# 01-MCU.net
KiCad netlist of a schematic drawn in Altium Designer
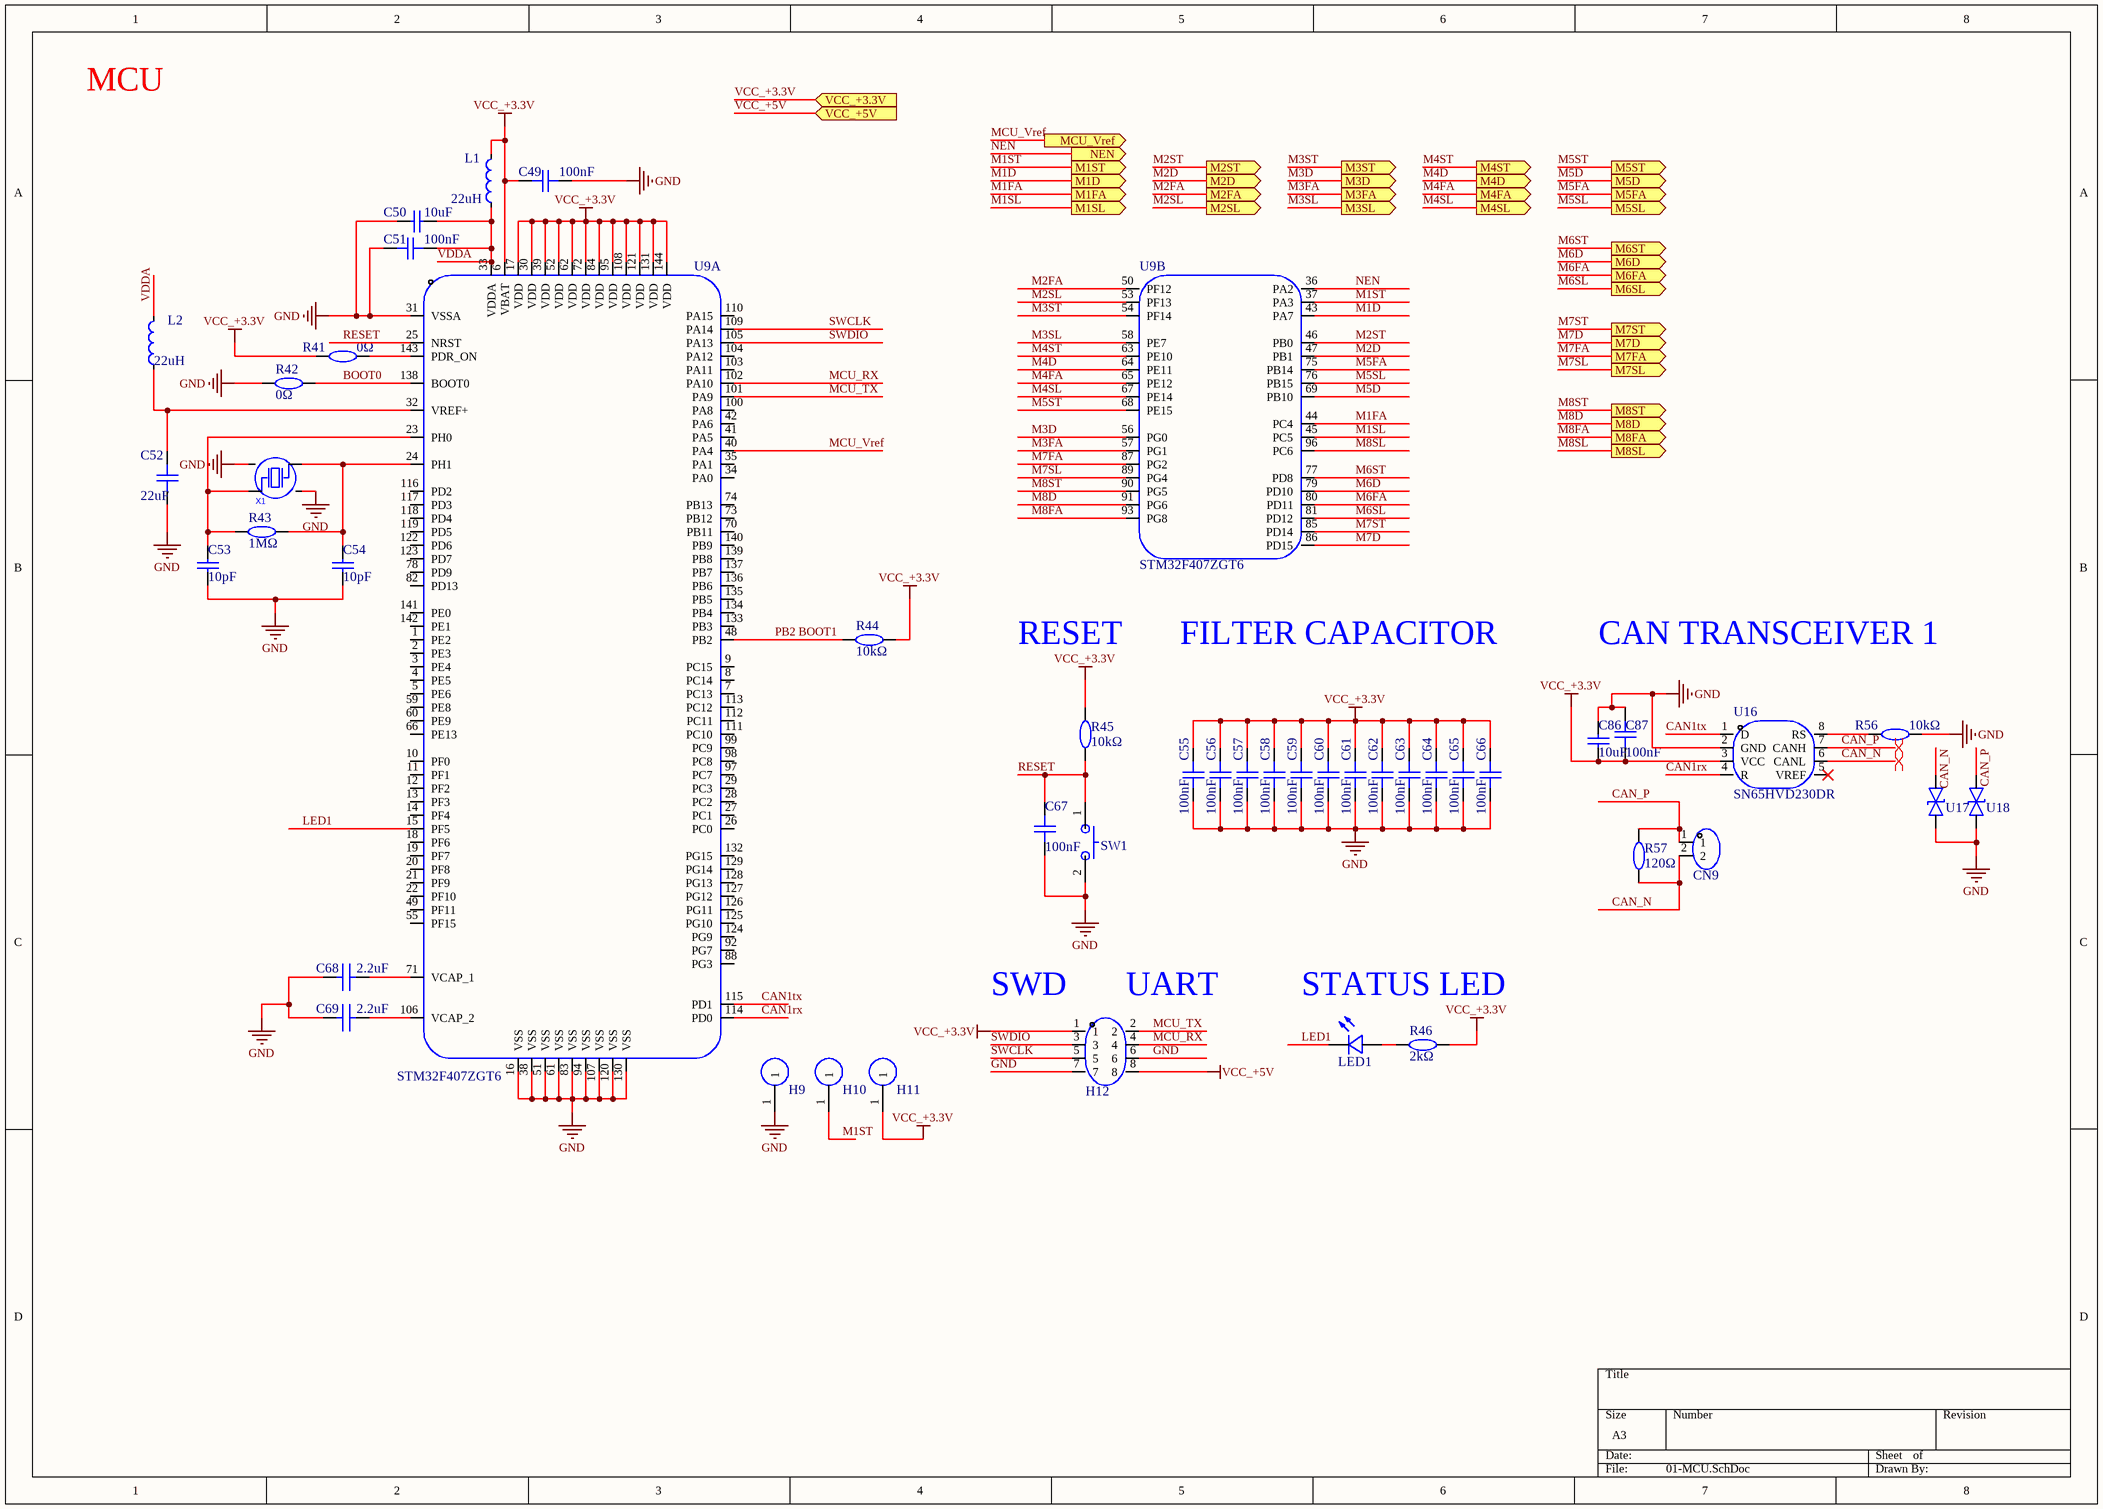
[diagram p0: 01-MCU.SchDoc]

(export (version "E")
  (design (tool "Eeschema 10.0.6"))
  (components
    (comp (ref "C49")
      (value "100nF")
      (footprint "C0402_2.2uF")
      (description "0402电容")
      (fields
        (field (name "MANUFACTURER") "muRata(村田)")
        (field (name "MANUFACTURER PART") "GRM155R71H104KE14D")
      )
      (libsource (lib "SchLib") (part "C0402_100nF"))
    )
    (comp (ref "C50")
      (value "10uF")
      (footprint "C0402_2.2uF")
      (description "0402电容")
      (fields
        (field (name "MANUFACTURER") "SAMSUNG(三星)")
        (field (name "MANUFACTURER PART") "CL05A106MQ5NUNC")
      )
      (libsource (lib "SchLib") (part "C0402_10uF"))
    )
    (comp (ref "C51")
      (value "100nF")
      (footprint "C0402_2.2uF")
      (description "0402电容")
      (fields
        (field (name "MANUFACTURER") "muRata(村田)")
        (field (name "MANUFACTURER PART") "GRM155R71H104KE14D")
      )
      (libsource (lib "SchLib") (part "C0402_100nF"))
    )
    (comp (ref "C52")
      (value "22uF")
      (footprint "C0603")
      (description "0603电容")
      (fields
        (field (name "MANUFACTURER") "SAMSUNG(三星)")
        (field (name "MANUFACTURER PART") "CC0603KRX7R9BB104")
      )
      (libsource (lib "SchLib") (part "C0603_22uF"))
    )
    (comp (ref "C53")
      (value "10pF")
      (footprint "C0402_2.2uF")
      (description "0402电容")
      (fields (field (name "MANUFACTURER") "FH(风华)") (field (name "MANUFACTURER PART") "0402CG100J500NT"))
      (libsource (lib "SchLib") (part "C0402_10pF"))
    )
    (comp (ref "C54")
      (value "10pF")
      (footprint "C0402_2.2uF")
      (description "0402电容")
      (fields (field (name "MANUFACTURER") "FH(风华)") (field (name "MANUFACTURER PART") "0402CG100J500NT"))
      (libsource (lib "SchLib") (part "C0402_10pF"))
    )
    (comp (ref "C55")
      (value "100nF")
      (footprint "C0402_2.2uF")
      (description "0402电容")
      (fields
        (field (name "MANUFACTURER") "muRata(村田)")
        (field (name "MANUFACTURER PART") "GRM155R71H104KE14D")
      )
      (libsource (lib "SchLib") (part "C0402_100nF"))
    )
    (comp (ref "C56")
      (value "100nF")
      (footprint "C0402_2.2uF")
      (description "0402电容")
      (fields
        (field (name "MANUFACTURER") "muRata(村田)")
        (field (name "MANUFACTURER PART") "GRM155R71H104KE14D")
      )
      (libsource (lib "SchLib") (part "C0402_100nF"))
    )
    (comp (ref "C57")
      (value "100nF")
      (footprint "C0402_2.2uF")
      (description "0402电容")
      (fields
        (field (name "MANUFACTURER") "muRata(村田)")
        (field (name "MANUFACTURER PART") "GRM155R71H104KE14D")
      )
      (libsource (lib "SchLib") (part "C0402_100nF"))
    )
    (comp (ref "C58")
      (value "100nF")
      (footprint "C0402_2.2uF")
      (description "0402电容")
      (fields
        (field (name "MANUFACTURER") "muRata(村田)")
        (field (name "MANUFACTURER PART") "GRM155R71H104KE14D")
      )
      (libsource (lib "SchLib") (part "C0402_100nF"))
    )
    (comp (ref "C59")
      (value "100nF")
      (footprint "C0402_2.2uF")
      (description "0402电容")
      (fields
        (field (name "MANUFACTURER") "muRata(村田)")
        (field (name "MANUFACTURER PART") "GRM155R71H104KE14D")
      )
      (libsource (lib "SchLib") (part "C0402_100nF"))
    )
    (comp (ref "C60")
      (value "100nF")
      (footprint "C0402_2.2uF")
      (description "0402电容")
      (fields
        (field (name "MANUFACTURER") "muRata(村田)")
        (field (name "MANUFACTURER PART") "GRM155R71H104KE14D")
      )
      (libsource (lib "SchLib") (part "C0402_100nF"))
    )
    (comp (ref "C61")
      (value "100nF")
      (footprint "C0402_2.2uF")
      (description "0402电容")
      (fields
        (field (name "MANUFACTURER") "muRata(村田)")
        (field (name "MANUFACTURER PART") "GRM155R71H104KE14D")
      )
      (libsource (lib "SchLib") (part "C0402_100nF"))
    )
    (comp (ref "C62")
      (value "100nF")
      (footprint "C0402_2.2uF")
      (description "0402电容")
      (fields
        (field (name "MANUFACTURER") "muRata(村田)")
        (field (name "MANUFACTURER PART") "GRM155R71H104KE14D")
      )
      (libsource (lib "SchLib") (part "C0402_100nF"))
    )
    (comp (ref "C63")
      (value "100nF")
      (footprint "C0402_2.2uF")
      (description "0402电容")
      (fields
        (field (name "MANUFACTURER") "muRata(村田)")
        (field (name "MANUFACTURER PART") "GRM155R71H104KE14D")
      )
      (libsource (lib "SchLib") (part "C0402_100nF"))
    )
    (comp (ref "C64")
      (value "100nF")
      (footprint "C0402_2.2uF")
      (description "0402电容")
      (fields
        (field (name "MANUFACTURER") "muRata(村田)")
        (field (name "MANUFACTURER PART") "GRM155R71H104KE14D")
      )
      (libsource (lib "SchLib") (part "C0402_100nF"))
    )
    (comp (ref "C65")
      (value "100nF")
      (footprint "C0402_2.2uF")
      (description "0402电容")
      (fields
        (field (name "MANUFACTURER") "muRata(村田)")
        (field (name "MANUFACTURER PART") "GRM155R71H104KE14D")
      )
      (libsource (lib "SchLib") (part "C0402_100nF"))
    )
    (comp (ref "C66")
      (value "100nF")
      (footprint "C0402_2.2uF")
      (description "0402电容")
      (fields
        (field (name "MANUFACTURER") "muRata(村田)")
        (field (name "MANUFACTURER PART") "GRM155R71H104KE14D")
      )
      (libsource (lib "SchLib") (part "C0402_100nF"))
    )
    (comp (ref "C67")
      (value "100nF")
      (footprint "C0603")
      (description "0603电容")
      (fields
        (field (name "MANUFACTURER") "SAMSUNG(三星)")
        (field (name "MANUFACTURER PART") "CC0603KRX7R9BB104")
      )
      (libsource (lib "SchLib") (part "C0603_100nF"))
    )
    (comp (ref "C68")
      (value "2.2uF")
      (footprint "C0402_2.2uF")
      (description "容值 2.2uF   精度 ±20%   额定电压 6.3V   材质(温度系数) X5R")
      (fields
        (field (name "MANUFACTURER") "SAMSUNG(三星)")
        (field (name "MANUFACTURER PART") "CL05A225MQ5NSNC")
      )
      (libsource (lib "SchLib") (part "C0402_2.2uF"))
    )
    (comp (ref "C69")
      (value "2.2uF")
      (footprint "C0402_2.2uF")
      (description "容值 2.2uF   精度 ±20%   额定电压 6.3V   材质(温度系数) X5R")
      (fields
        (field (name "MANUFACTURER") "SAMSUNG(三星)")
        (field (name "MANUFACTURER PART") "CL05A225MQ5NSNC")
      )
      (libsource (lib "SchLib") (part "C0402_2.2uF"))
    )
    (comp (ref "C86")
      (value "10uF")
      (footprint "C0402_2.2uF")
      (description "0402电容")
      (fields
        (field (name "MANUFACTURER") "SAMSUNG(三星)")
        (field (name "MANUFACTURER PART") "CL05A106MQ5NUNC")
      )
      (libsource (lib "SchLib") (part "C0402_10uF"))
    )
    (comp (ref "C87")
      (value "100nF")
      (footprint "C0402_2.2uF")
      (description "0402电容")
      (fields
        (field (name "MANUFACTURER") "muRata(村田)")
        (field (name "MANUFACTURER PART") "GRM155R71H104KE14D")
      )
      (libsource (lib "SchLib") (part "C0402_100nF"))
    )
    (comp (ref "CN9")
      (value "ZX-XH2.54-2PZZ")
      (footprint "ZX-XH2.54-2PZZ")
      (description "直插插针")
      (fields (field (name "MANUFACTURER") "Megastar(兆星)"))
      (libsource (lib "SchLib") (part "ZX-XH2.54-2PZZ"))
    )
    (comp (ref "H9")
      (value "PZ254V-11-01P")
      (footprint "Testpoint")
      (description "测试点")
      (fields (field (name "MANUFACTURER") "XFCN(兴飞)"))
      (libsource (lib "SchLib") (part "Testpoint"))
    )
    (comp (ref "H10")
      (value "PZ254V-11-01P")
      (footprint "Testpoint")
      (description "测试点")
      (fields (field (name "MANUFACTURER") "XFCN(兴飞)"))
      (libsource (lib "SchLib") (part "Testpoint"))
    )
    (comp (ref "H11")
      (value "PZ254V-11-01P")
      (footprint "Testpoint")
      (description "测试点")
      (fields (field (name "MANUFACTURER") "XFCN(兴飞)"))
      (libsource (lib "SchLib") (part "Testpoint"))
    )
    (comp (ref "H12")
      (value "PZ254V-12-8P")
      (footprint "HC-1.25-8PLT")
      (description "排针8P")
      (fields (field (name "MANUFACTURER") "XFCN(兴飞)"))
      (libsource (lib "SchLib") (part "HC-1.25-8PLT"))
    )
    (comp (ref "L1")
      (value "22uH")
      (footprint "L0603_22uH")
      (description "0603电感")
      (fields (field (name "MANUFACTURER") "TDK") (field (name "MANUFACTURER PART") "MLZ1608M220WT000"))
      (libsource (lib "SchLib") (part "L0603_22uH"))
    )
    (comp (ref "L2")
      (value "22uH")
      (footprint "L0603_22uH")
      (description "0603电感")
      (fields (field (name "MANUFACTURER") "TDK") (field (name "MANUFACTURER PART") "MLZ1608M220WT000"))
      (libsource (lib "SchLib") (part "L0603_22uH"))
    )
    (comp (ref "LED1")
      (value "MHT192UGCT")
      (footprint "LED")
      (description "发光二极管 绿色")
      (fields (field (name "MANUFACTURER") "MEIHUA(美华)"))
      (libsource (lib "SchLib") (part "LED"))
    )
    (comp (ref "R41")
      (value "0Ω")
      (footprint "R0603")
      (description "阻值 0Ω   精度 ±1%   功率 100mW   最大工作电压 75V   工作温度范围 -55℃~+155℃")
      (fields
        (field (name "MANUFACTURER") "UNI-ROYAL(厚声)")
        (field (name "MANUFACTURER PART") "0603WAF0000T5E")
      )
      (libsource (lib "SchLib") (part "R0603_0Ω"))
    )
    (comp (ref "R42")
      (value "0Ω")
      (footprint "R0603")
      (description "阻值 0Ω   精度 ±1%   功率 100mW   最大工作电压 75V   工作温度范围 -55℃~+155℃")
      (fields
        (field (name "MANUFACTURER") "UNI-ROYAL(厚声)")
        (field (name "MANUFACTURER PART") "0603WAF0000T5E")
      )
      (libsource (lib "SchLib") (part "R0603_0Ω"))
    )
    (comp (ref "R43")
      (value "1MΩ")
      (footprint "R0603")
      (description "0603电阻")
      (fields
        (field (name "MANUFACTURER") "UNI-ROYAL(厚声)")
        (field (name "MANUFACTURER PART") "0603WAF5100T5E")
      )
      (libsource (lib "SchLib") (part "R0603_1MΩ"))
    )
    (comp (ref "R44")
      (value "10kΩ")
      (footprint "R0603_10KΩ")
      (description "0603电阻")
      (fields
        (field (name "MANUFACTURER") "UNI-ROYAL(厚声)")
        (field (name "MANUFACTURER PART") "0603WAF1002T5E")
      )
      (libsource (lib "SchLib") (part "R0603_10KΩ"))
    )
    (comp (ref "R45")
      (value "10kΩ")
      (footprint "R0603_10KΩ")
      (description "0603电阻")
      (fields
        (field (name "MANUFACTURER") "UNI-ROYAL(厚声)")
        (field (name "MANUFACTURER PART") "0603WAF1002T5E")
      )
      (libsource (lib "SchLib") (part "R0603_10KΩ"))
    )
    (comp (ref "R46")
      (value "2kΩ")
      (footprint "R0603")
      (description "0603电阻")
      (fields
        (field (name "MANUFACTURER") "UNI-ROYAL(厚声)")
        (field (name "MANUFACTURER PART") "0603WAF2001T5E")
      )
      (libsource (lib "SchLib") (part "R0603_2KΩ"))
    )
    (comp (ref "R56")
      (value "10kΩ")
      (footprint "R0603")
      (description "0603电阻")
      (fields
        (field (name "MANUFACTURER") "UNI-ROYAL(厚声)")
        (field (name "MANUFACTURER PART") "0603WAF1002T5E")
      )
      (libsource (lib "SchLib") (part "R0603_10KΩ"))
    )
    (comp (ref "R57")
      (value "120Ω")
      (footprint "R0603")
      (description "0603电阻")
      (fields
        (field (name "MANUFACTURER") "UNI-ROYAL(厚声)")
        (field (name "MANUFACTURER PART") "0603WAF1200T5E")
      )
      (libsource (lib "SchLib") (part "R0603_120Ω"))
    )
    (comp (ref "SW1")
      (value "GT-TC029B-H020-L1N")
      (footprint "Switch")
      (fields (field (name "MANUFACTURER") "G-Switch(品赞)"))
      (libsource (lib "SchLib") (part "Switch"))
    )
    (comp (ref "U9")
      (value "STM32F407ZGT6")
      (footprint "STM32F407ZGT6")
      (fields (field (name "MANUFACTURER") "ST(意法半导体)"))
      (libsource (lib "SchLib") (part "STM32F407ZGT6"))
    )
    (comp (ref "U16")
      (value "SN65HVD230DR")
      (footprint "SN65HVD230DR")
      (description "CAN收发器")
      (fields (field (name "MANUFACTURER") "TI(德州仪器)"))
      (libsource (lib "SchLib") (part "SN65HVD230DR"))
    )
    (comp (ref "U17")
      (value "PESD0603-240")
      (footprint "PESD0603-240")
      (description "ESD")
      (fields (field (name "MANUFACTURER") "Littelfuse(美国力特)"))
      (libsource (lib "SchLib") (part "PESD0603-240"))
    )
    (comp (ref "U18")
      (value "PESD0603-240")
      (footprint "PESD0603-240")
      (description "ESD")
      (fields (field (name "MANUFACTURER") "Littelfuse(美国力特)"))
      (libsource (lib "SchLib") (part "PESD0603-240"))
    )
    (comp (ref "X1")
      (value "8MHz")
      (footprint "Osc_8M")
      (description "8Mhz晶振")
      (fields (field (name "MANUFACTURER") "YJX(雅晶鑫)") (field (name "MANUFACTURER PART") "TAXM8M4RDBCCT2T"))
      (libsource (lib "SchLib") (part "Osc_8M"))
    )
  )
  (nets
    (net (code "1") (name "/BOOT0") (class "Default")
      (node (ref "R42") (pin "2") (pinfunction "2_2") (pintype "passive"))
      (node (ref "U9") (pin "138") (pinfunction "BOOT0_138") (pintype "passive"))
    )
    (net (code "2") (name "/CAN1rx") (class "Default")
      (node (ref "U16") (pin "4") (pinfunction "R_4") (pintype "passive"))
      (node (ref "U9") (pin "114") (pinfunction "PD0_114") (pintype "passive"))
    )
    (net (code "3") (name "/CAN1tx") (class "Default")
      (node (ref "U16") (pin "1") (pinfunction "D_1") (pintype "passive"))
      (node (ref "U9") (pin "115") (pinfunction "PD1_115") (pintype "passive"))
    )
    (net (code "4") (name "/CAN_N") (class "Default")
      (node (ref "CN9") (pin "2") (pinfunction "2_2") (pintype "passive"))
      (node (ref "R57") (pin "1") (pinfunction "1_1") (pintype "passive"))
      (node (ref "U16") (pin "6") (pinfunction "CANL_6") (pintype "passive"))
      (node (ref "U17") (pin "2") (pinfunction "2_2") (pintype "passive"))
    )
    (net (code "5") (name "/CAN_P") (class "Default")
      (node (ref "CN9") (pin "1") (pinfunction "1_1") (pintype "passive"))
      (node (ref "R57") (pin "2") (pinfunction "2_2") (pintype "passive"))
      (node (ref "U16") (pin "7") (pinfunction "CANH_7") (pintype "passive"))
      (node (ref "U18") (pin "2") (pinfunction "2_2") (pintype "passive"))
    )
    (net (code "6") (name "/LED1") (class "Default")
      (node (ref "LED1") (pin "1") (pinfunction "-_1") (pintype "passive"))
      (node (ref "U9") (pin "15") (pinfunction "PF5_15") (pintype "passive"))
    )
    (net (code "7") (name "/M1D") (class "Default")
      (node (ref "U9") (pin "43") (pinfunction "PA7_43") (pintype "passive"))
    )
    (net (code "8") (name "/M1FA") (class "Default")
      (node (ref "U9") (pin "44") (pinfunction "PC4_44") (pintype "passive"))
    )
    (net (code "9") (name "/M1SL") (class "Default")
      (node (ref "U9") (pin "45") (pinfunction "PC5_45") (pintype "passive"))
    )
    (net (code "10") (name "/M1ST") (class "Default")
      (node (ref "H10") (pin "1") (pinfunction "1_1") (pintype "passive"))
      (node (ref "U9") (pin "37") (pinfunction "PA3_37") (pintype "passive"))
    )
    (net (code "11") (name "/M2D") (class "Default")
      (node (ref "U9") (pin "47") (pinfunction "PB1_47") (pintype "passive"))
    )
    (net (code "12") (name "/M2FA") (class "Default")
      (node (ref "U9") (pin "50") (pinfunction "PF12_50") (pintype "passive"))
    )
    (net (code "13") (name "/M2SL") (class "Default")
      (node (ref "U9") (pin "53") (pinfunction "PF13_53") (pintype "passive"))
    )
    (net (code "14") (name "/M2ST") (class "Default")
      (node (ref "U9") (pin "46") (pinfunction "PB0_46") (pintype "passive"))
    )
    (net (code "15") (name "/M3D") (class "Default")
      (node (ref "U9") (pin "56") (pinfunction "PG0_56") (pintype "passive"))
    )
    (net (code "16") (name "/M3FA") (class "Default")
      (node (ref "U9") (pin "57") (pinfunction "PG1_57") (pintype "passive"))
    )
    (net (code "17") (name "/M3SL") (class "Default")
      (node (ref "U9") (pin "58") (pinfunction "PE7_58") (pintype "passive"))
    )
    (net (code "18") (name "/M3ST") (class "Default")
      (node (ref "U9") (pin "54") (pinfunction "PF14_54") (pintype "passive"))
    )
    (net (code "19") (name "/M4D") (class "Default")
      (node (ref "U9") (pin "64") (pinfunction "PE11_64") (pintype "passive"))
    )
    (net (code "20") (name "/M4FA") (class "Default")
      (node (ref "U9") (pin "65") (pinfunction "PE12_65") (pintype "passive"))
    )
    (net (code "21") (name "/M4SL") (class "Default")
      (node (ref "U9") (pin "67") (pinfunction "PE14_67") (pintype "passive"))
    )
    (net (code "22") (name "/M4ST") (class "Default")
      (node (ref "U9") (pin "63") (pinfunction "PE10_63") (pintype "passive"))
    )
    (net (code "23") (name "/M5D") (class "Default")
      (node (ref "U9") (pin "69") (pinfunction "PB10_69") (pintype "passive"))
    )
    (net (code "24") (name "/M5FA") (class "Default")
      (node (ref "U9") (pin "75") (pinfunction "PB14_75") (pintype "passive"))
    )
    (net (code "25") (name "/M5SL") (class "Default")
      (node (ref "U9") (pin "76") (pinfunction "PB15_76") (pintype "passive"))
    )
    (net (code "26") (name "/M5ST") (class "Default")
      (node (ref "U9") (pin "68") (pinfunction "PE15_68") (pintype "passive"))
    )
    (net (code "27") (name "/M6D") (class "Default")
      (node (ref "U9") (pin "79") (pinfunction "PD10_79") (pintype "passive"))
    )
    (net (code "28") (name "/M6FA") (class "Default")
      (node (ref "U9") (pin "80") (pinfunction "PD11_80") (pintype "passive"))
    )
    (net (code "29") (name "/M6SL") (class "Default")
      (node (ref "U9") (pin "81") (pinfunction "PD12_81") (pintype "passive"))
    )
    (net (code "30") (name "/M6ST") (class "Default")
      (node (ref "U9") (pin "77") (pinfunction "PD8_77") (pintype "passive"))
    )
    (net (code "31") (name "/M7D") (class "Default")
      (node (ref "U9") (pin "86") (pinfunction "PD15_86") (pintype "passive"))
    )
    (net (code "32") (name "/M7FA") (class "Default")
      (node (ref "U9") (pin "87") (pinfunction "PG2_87") (pintype "passive"))
    )
    (net (code "33") (name "/M7SL") (class "Default")
      (node (ref "U9") (pin "89") (pinfunction "PG4_89") (pintype "passive"))
    )
    (net (code "34") (name "/M7ST") (class "Default")
      (node (ref "U9") (pin "85") (pinfunction "PD14_85") (pintype "passive"))
    )
    (net (code "35") (name "/M8D") (class "Default")
      (node (ref "U9") (pin "91") (pinfunction "PG6_91") (pintype "passive"))
    )
    (net (code "36") (name "/M8FA") (class "Default")
      (node (ref "U9") (pin "93") (pinfunction "PG8_93") (pintype "passive"))
    )
    (net (code "37") (name "/M8SL") (class "Default")
      (node (ref "U9") (pin "96") (pinfunction "PC6_96") (pintype "passive"))
    )
    (net (code "38") (name "/M8ST") (class "Default")
      (node (ref "U9") (pin "90") (pinfunction "PG5_90") (pintype "passive"))
    )
    (net (code "39") (name "/MCU_RX") (class "Default")
      (node (ref "H12") (pin "4") (pinfunction "4_4") (pintype "passive"))
      (node (ref "U9") (pin "102") (pinfunction "PA10_102") (pintype "passive"))
    )
    (net (code "40") (name "/MCU_TX") (class "Default")
      (node (ref "H12") (pin "2") (pinfunction "2_2") (pintype "passive"))
      (node (ref "U9") (pin "101") (pinfunction "PA9_101") (pintype "passive"))
    )
    (net (code "41") (name "/MCU_Vref") (class "Default")
      (node (ref "U9") (pin "40") (pinfunction "PA4_40") (pintype "passive"))
    )
    (net (code "42") (name "/NEN") (class "Default")
      (node (ref "U9") (pin "36") (pinfunction "PA2_36") (pintype "passive"))
    )
    (net (code "43") (name "/PB2 BOOT1") (class "Default")
      (node (ref "R44") (pin "1") (pinfunction "1_1") (pintype "passive"))
      (node (ref "U9") (pin "48") (pinfunction "PB2_48") (pintype "passive"))
    )
    (net (code "44") (name "/RESET") (class "Default")
      (node (ref "C67") (pin "2") (pinfunction "2_2") (pintype "passive"))
      (node (ref "R45") (pin "1") (pinfunction "1_1") (pintype "passive"))
      (node (ref "SW1") (pin "1") (pinfunction "1_1") (pintype "passive"))
      (node (ref "U9") (pin "25") (pinfunction "NRST_25") (pintype "passive"))
    )
    (net (code "45") (name "/SWCLK") (class "Default")
      (node (ref "H12") (pin "5") (pinfunction "5_5") (pintype "passive"))
      (node (ref "U9") (pin "109") (pinfunction "PA14_109") (pintype "passive"))
    )
    (net (code "46") (name "/SWDIO") (class "Default")
      (node (ref "H12") (pin "3") (pinfunction "3_3") (pintype "passive"))
      (node (ref "U9") (pin "105") (pinfunction "PA13_105") (pintype "passive"))
    )
    (net (code "47") (name "/VDDA") (class "Default")
      (node (ref "C50") (pin "2") (pinfunction "2_2") (pintype "passive"))
      (node (ref "C51") (pin "2") (pinfunction "2_2") (pintype "passive"))
      (node (ref "L1") (pin "1") (pinfunction "1_1") (pintype "passive"))
      (node (ref "L2") (pin "2") (pinfunction "2_2") (pintype "passive"))
      (node (ref "U9") (pin "33") (pinfunction "VDDA_33") (pintype "passive"))
    )
    (net (code "48") (name "GND") (class "Default")
      (node (ref "C49") (pin "2") (pinfunction "2_2") (pintype "passive"))
      (node (ref "C50") (pin "1") (pinfunction "1_1") (pintype "passive"))
      (node (ref "C51") (pin "1") (pinfunction "1_1") (pintype "passive"))
      (node (ref "C52") (pin "1") (pinfunction "1_1") (pintype "passive"))
      (node (ref "C53") (pin "1") (pinfunction "1_1") (pintype "passive"))
      (node (ref "C54") (pin "1") (pinfunction "1_1") (pintype "passive"))
      (node (ref "C55") (pin "2") (pinfunction "2_2") (pintype "passive"))
      (node (ref "C56") (pin "2") (pinfunction "2_2") (pintype "passive"))
      (node (ref "C57") (pin "2") (pinfunction "2_2") (pintype "passive"))
      (node (ref "C58") (pin "2") (pinfunction "2_2") (pintype "passive"))
      (node (ref "C59") (pin "2") (pinfunction "2_2") (pintype "passive"))
      (node (ref "C60") (pin "2") (pinfunction "2_2") (pintype "passive"))
      (node (ref "C61") (pin "2") (pinfunction "2_2") (pintype "passive"))
      (node (ref "C62") (pin "2") (pinfunction "2_2") (pintype "passive"))
      (node (ref "C63") (pin "2") (pinfunction "2_2") (pintype "passive"))
      (node (ref "C64") (pin "2") (pinfunction "2_2") (pintype "passive"))
      (node (ref "C65") (pin "2") (pinfunction "2_2") (pintype "passive"))
      (node (ref "C66") (pin "2") (pinfunction "2_2") (pintype "passive"))
      (node (ref "C67") (pin "1") (pinfunction "1_1") (pintype "passive"))
      (node (ref "C68") (pin "1") (pinfunction "1_1") (pintype "passive"))
      (node (ref "C69") (pin "1") (pinfunction "1_1") (pintype "passive"))
      (node (ref "C86") (pin "2") (pinfunction "2_2") (pintype "passive"))
      (node (ref "C87") (pin "2") (pinfunction "2_2") (pintype "passive"))
      (node (ref "H12") (pin "6") (pinfunction "6_6") (pintype "passive"))
      (node (ref "H12") (pin "7") (pinfunction "7_7") (pintype "passive"))
      (node (ref "H9") (pin "1") (pinfunction "1_1") (pintype "passive"))
      (node (ref "R42") (pin "1") (pinfunction "1_1") (pintype "passive"))
      (node (ref "R56") (pin "2") (pinfunction "2_2") (pintype "passive"))
      (node (ref "SW1") (pin "2") (pinfunction "2_2") (pintype "passive"))
      (node (ref "U16") (pin "2") (pinfunction "GND_2") (pintype "passive"))
      (node (ref "U17") (pin "1") (pinfunction "1_1") (pintype "passive"))
      (node (ref "U18") (pin "1") (pinfunction "1_1") (pintype "passive"))
      (node (ref "U9") (pin "107") (pinfunction "VSS_107") (pintype "passive"))
      (node (ref "U9") (pin "120") (pinfunction "VSS_120") (pintype "passive"))
      (node (ref "U9") (pin "130") (pinfunction "VSS_130") (pintype "passive"))
      (node (ref "U9") (pin "16") (pinfunction "VSS_16") (pintype "passive"))
      (node (ref "U9") (pin "31") (pinfunction "VSSA_31") (pintype "passive"))
      (node (ref "U9") (pin "38") (pinfunction "VSS_38") (pintype "passive"))
      (node (ref "U9") (pin "51") (pinfunction "VSS_51") (pintype "passive"))
      (node (ref "U9") (pin "61") (pinfunction "VSS_61") (pintype "passive"))
      (node (ref "U9") (pin "83") (pinfunction "VSS_83") (pintype "passive"))
      (node (ref "U9") (pin "94") (pinfunction "VSS_94") (pintype "passive"))
      (node (ref "X1") (pin "2") (pinfunction "2_2") (pintype "passive"))
      (node (ref "X1") (pin "4") (pinfunction "4_4") (pintype "passive"))
    )
    (net (code "49") (name "Net-(LED1-+)") (class "Default")
      (node (ref "LED1") (pin "2") (pinfunction "+_2") (pintype "passive"))
      (node (ref "R46") (pin "1") (pinfunction "1_1") (pintype "passive"))
    )
    (net (code "50") (name "Net-(U9A-PDR_ON)") (class "Default")
      (node (ref "R41") (pin "2") (pinfunction "2_2") (pintype "passive"))
      (node (ref "U9") (pin "143") (pinfunction "PDR_ON_143") (pintype "passive"))
    )
    (net (code "51") (name "Net-(U9A-PH0)") (class "Default")
      (node (ref "C53") (pin "2") (pinfunction "2_2") (pintype "passive"))
      (node (ref "R43") (pin "1") (pinfunction "1_1") (pintype "passive"))
      (node (ref "U9") (pin "23") (pinfunction "PH0_23") (pintype "passive"))
      (node (ref "X1") (pin "1") (pinfunction "1_1") (pintype "passive"))
    )
    (net (code "52") (name "Net-(U9A-PH1)") (class "Default")
      (node (ref "C54") (pin "2") (pinfunction "2_2") (pintype "passive"))
      (node (ref "R43") (pin "2") (pinfunction "2_2") (pintype "passive"))
      (node (ref "U9") (pin "24") (pinfunction "PH1_24") (pintype "passive"))
      (node (ref "X1") (pin "3") (pinfunction "3_3") (pintype "passive"))
    )
    (net (code "53") (name "Net-(U9A-VCAP_1)") (class "Default")
      (node (ref "C68") (pin "2") (pinfunction "2_2") (pintype "passive"))
      (node (ref "U9") (pin "71") (pinfunction "VCAP_1_71") (pintype "passive"))
    )
    (net (code "54") (name "Net-(U9A-VCAP_2)") (class "Default")
      (node (ref "C69") (pin "2") (pinfunction "2_2") (pintype "passive"))
      (node (ref "U9") (pin "106") (pinfunction "VCAP_2_106") (pintype "passive"))
    )
    (net (code "55") (name "Net-(U9A-VREF+)") (class "Default")
      (node (ref "C52") (pin "2") (pinfunction "2_2") (pintype "passive"))
      (node (ref "L2") (pin "1") (pinfunction "1_1") (pintype "passive"))
      (node (ref "U9") (pin "32") (pinfunction "VREF+_32") (pintype "passive"))
    )
    (net (code "56") (name "Net-(U16-RS)") (class "Default")
      (node (ref "R56") (pin "1") (pinfunction "1_1") (pintype "passive"))
      (node (ref "U16") (pin "8") (pinfunction "RS_8") (pintype "passive"))
    )
    (net (code "57") (name "VCC_+3.3V") (class "Default")
      (node (ref "C49") (pin "1") (pinfunction "1_1") (pintype "passive"))
      (node (ref "C55") (pin "1") (pinfunction "1_1") (pintype "passive"))
      (node (ref "C56") (pin "1") (pinfunction "1_1") (pintype "passive"))
      (node (ref "C57") (pin "1") (pinfunction "1_1") (pintype "passive"))
      (node (ref "C58") (pin "1") (pinfunction "1_1") (pintype "passive"))
      (node (ref "C59") (pin "1") (pinfunction "1_1") (pintype "passive"))
      (node (ref "C60") (pin "1") (pinfunction "1_1") (pintype "passive"))
      (node (ref "C61") (pin "1") (pinfunction "1_1") (pintype "passive"))
      (node (ref "C62") (pin "1") (pinfunction "1_1") (pintype "passive"))
      (node (ref "C63") (pin "1") (pinfunction "1_1") (pintype "passive"))
      (node (ref "C64") (pin "1") (pinfunction "1_1") (pintype "passive"))
      (node (ref "C65") (pin "1") (pinfunction "1_1") (pintype "passive"))
      (node (ref "C66") (pin "1") (pinfunction "1_1") (pintype "passive"))
      (node (ref "C86") (pin "1") (pinfunction "1_1") (pintype "passive"))
      (node (ref "C87") (pin "1") (pinfunction "1_1") (pintype "passive"))
      (node (ref "H11") (pin "1") (pinfunction "1_1") (pintype "passive"))
      (node (ref "H12") (pin "1") (pinfunction "1_1") (pintype "passive"))
      (node (ref "L1") (pin "2") (pinfunction "2_2") (pintype "passive"))
      (node (ref "R41") (pin "1") (pinfunction "1_1") (pintype "passive"))
      (node (ref "R44") (pin "2") (pinfunction "2_2") (pintype "passive"))
      (node (ref "R45") (pin "2") (pinfunction "2_2") (pintype "passive"))
      (node (ref "R46") (pin "2") (pinfunction "2_2") (pintype "passive"))
      (node (ref "U16") (pin "3") (pinfunction "VCC_3") (pintype "passive"))
      (node (ref "U9") (pin "108") (pinfunction "VDD_108") (pintype "passive"))
      (node (ref "U9") (pin "121") (pinfunction "VDD_121") (pintype "passive"))
      (node (ref "U9") (pin "131") (pinfunction "VDD_131") (pintype "passive"))
      (node (ref "U9") (pin "144") (pinfunction "VDD_144") (pintype "passive"))
      (node (ref "U9") (pin "17") (pinfunction "VDD_17") (pintype "passive"))
      (node (ref "U9") (pin "30") (pinfunction "VDD_30") (pintype "passive"))
      (node (ref "U9") (pin "39") (pinfunction "VDD_39") (pintype "passive"))
      (node (ref "U9") (pin "52") (pinfunction "VDD_52") (pintype "passive"))
      (node (ref "U9") (pin "6") (pinfunction "VBAT_6") (pintype "passive"))
      (node (ref "U9") (pin "62") (pinfunction "VDD_62") (pintype "passive"))
      (node (ref "U9") (pin "72") (pinfunction "VDD_72") (pintype "passive"))
      (node (ref "U9") (pin "84") (pinfunction "VDD_84") (pintype "passive"))
      (node (ref "U9") (pin "95") (pinfunction "VDD_95") (pintype "passive"))
    )
    (net (code "58") (name "VCC_+5V") (class "Default")
      (node (ref "H12") (pin "8") (pinfunction "8_8") (pintype "passive"))
    )
    (net (code "59") (name "unconnected-(U9A-PA0-Pad34)") (class "Default")
      (node (ref "U9") (pin "34") (pinfunction "PA0_34") (pintype "passive"))
    )
    (net (code "60") (name "unconnected-(U9A-PA1-Pad35)") (class "Default")
      (node (ref "U9") (pin "35") (pinfunction "PA1_35") (pintype "passive"))
    )
    (net (code "61") (name "unconnected-(U9A-PA5-Pad41)") (class "Default")
      (node (ref "U9") (pin "41") (pinfunction "PA5_41") (pintype "passive"))
    )
    (net (code "62") (name "unconnected-(U9A-PA6-Pad42)") (class "Default")
      (node (ref "U9") (pin "42") (pinfunction "PA6_42") (pintype "passive"))
    )
    (net (code "63") (name "unconnected-(U9A-PA8-Pad100)") (class "Default")
      (node (ref "U9") (pin "100") (pinfunction "PA8_100") (pintype "passive"))
    )
    (net (code "64") (name "unconnected-(U9A-PA11-Pad103)") (class "Default")
      (node (ref "U9") (pin "103") (pinfunction "PA11_103") (pintype "passive"))
    )
    (net (code "65") (name "unconnected-(U9A-PA12-Pad104)") (class "Default")
      (node (ref "U9") (pin "104") (pinfunction "PA12_104") (pintype "passive"))
    )
    (net (code "66") (name "unconnected-(U9A-PA15-Pad110)") (class "Default")
      (node (ref "U9") (pin "110") (pinfunction "PA15_110") (pintype "passive"))
    )
    (net (code "67") (name "unconnected-(U9A-PB3-Pad133)") (class "Default")
      (node (ref "U9") (pin "133") (pinfunction "PB3_133") (pintype "passive"))
    )
    (net (code "68") (name "unconnected-(U9A-PB4-Pad134)") (class "Default")
      (node (ref "U9") (pin "134") (pinfunction "PB4_134") (pintype "passive"))
    )
    (net (code "69") (name "unconnected-(U9A-PB5-Pad135)") (class "Default")
      (node (ref "U9") (pin "135") (pinfunction "PB5_135") (pintype "passive"))
    )
    (net (code "70") (name "unconnected-(U9A-PB6-Pad136)") (class "Default")
      (node (ref "U9") (pin "136") (pinfunction "PB6_136") (pintype "passive"))
    )
    (net (code "71") (name "unconnected-(U9A-PB7-Pad137)") (class "Default")
      (node (ref "U9") (pin "137") (pinfunction "PB7_137") (pintype "passive"))
    )
    (net (code "72") (name "unconnected-(U9A-PB8-Pad139)") (class "Default")
      (node (ref "U9") (pin "139") (pinfunction "PB8_139") (pintype "passive"))
    )
    (net (code "73") (name "unconnected-(U9A-PB9-Pad140)") (class "Default")
      (node (ref "U9") (pin "140") (pinfunction "PB9_140") (pintype "passive"))
    )
    (net (code "74") (name "unconnected-(U9A-PB11-Pad70)") (class "Default")
      (node (ref "U9") (pin "70") (pinfunction "PB11_70") (pintype "passive"))
    )
    (net (code "75") (name "unconnected-(U9A-PB12-Pad73)") (class "Default")
      (node (ref "U9") (pin "73") (pinfunction "PB12_73") (pintype "passive"))
    )
    (net (code "76") (name "unconnected-(U9A-PB13-Pad74)") (class "Default")
      (node (ref "U9") (pin "74") (pinfunction "PB13_74") (pintype "passive"))
    )
    (net (code "77") (name "unconnected-(U9A-PC0-Pad26)") (class "Default")
      (node (ref "U9") (pin "26") (pinfunction "PC0_26") (pintype "passive"))
    )
    (net (code "78") (name "unconnected-(U9A-PC1-Pad27)") (class "Default")
      (node (ref "U9") (pin "27") (pinfunction "PC1_27") (pintype "passive"))
    )
    (net (code "79") (name "unconnected-(U9A-PC2-Pad28)") (class "Default")
      (node (ref "U9") (pin "28") (pinfunction "PC2_28") (pintype "passive"))
    )
    (net (code "80") (name "unconnected-(U9A-PC3-Pad29)") (class "Default")
      (node (ref "U9") (pin "29") (pinfunction "PC3_29") (pintype "passive"))
    )
    (net (code "81") (name "unconnected-(U9A-PC7-Pad97)") (class "Default")
      (node (ref "U9") (pin "97") (pinfunction "PC7_97") (pintype "passive"))
    )
    (net (code "82") (name "unconnected-(U9A-PC8-Pad98)") (class "Default")
      (node (ref "U9") (pin "98") (pinfunction "PC8_98") (pintype "passive"))
    )
    (net (code "83") (name "unconnected-(U9A-PC9-Pad99)") (class "Default")
      (node (ref "U9") (pin "99") (pinfunction "PC9_99") (pintype "passive"))
    )
    (net (code "84") (name "unconnected-(U9A-PC10-Pad111)") (class "Default")
      (node (ref "U9") (pin "111") (pinfunction "PC10_111") (pintype "passive"))
    )
    (net (code "85") (name "unconnected-(U9A-PC11-Pad112)") (class "Default")
      (node (ref "U9") (pin "112") (pinfunction "PC11_112") (pintype "passive"))
    )
    (net (code "86") (name "unconnected-(U9A-PC12-Pad113)") (class "Default")
      (node (ref "U9") (pin "113") (pinfunction "PC12_113") (pintype "passive"))
    )
    (net (code "87") (name "unconnected-(U9A-PC13-Pad7)") (class "Default")
      (node (ref "U9") (pin "7") (pinfunction "PC13_7") (pintype "passive"))
    )
    (net (code "88") (name "unconnected-(U9A-PC14-Pad8)") (class "Default")
      (node (ref "U9") (pin "8") (pinfunction "PC14_8") (pintype "passive"))
    )
    (net (code "89") (name "unconnected-(U9A-PC15-Pad9)") (class "Default")
      (node (ref "U9") (pin "9") (pinfunction "PC15_9") (pintype "passive"))
    )
    (net (code "90") (name "unconnected-(U9A-PD2-Pad116)") (class "Default")
      (node (ref "U9") (pin "116") (pinfunction "PD2_116") (pintype "passive"))
    )
    (net (code "91") (name "unconnected-(U9A-PD3-Pad117)") (class "Default")
      (node (ref "U9") (pin "117") (pinfunction "PD3_117") (pintype "passive"))
    )
    (net (code "92") (name "unconnected-(U9A-PD4-Pad118)") (class "Default")
      (node (ref "U9") (pin "118") (pinfunction "PD4_118") (pintype "passive"))
    )
    (net (code "93") (name "unconnected-(U9A-PD5-Pad119)") (class "Default")
      (node (ref "U9") (pin "119") (pinfunction "PD5_119") (pintype "passive"))
    )
    (net (code "94") (name "unconnected-(U9A-PD6-Pad122)") (class "Default")
      (node (ref "U9") (pin "122") (pinfunction "PD6_122") (pintype "passive"))
    )
    (net (code "95") (name "unconnected-(U9A-PD7-Pad123)") (class "Default")
      (node (ref "U9") (pin "123") (pinfunction "PD7_123") (pintype "passive"))
    )
    (net (code "96") (name "unconnected-(U9A-PD9-Pad78)") (class "Default")
      (node (ref "U9") (pin "78") (pinfunction "PD9_78") (pintype "passive"))
    )
    (net (code "97") (name "unconnected-(U9A-PD13-Pad82)") (class "Default")
      (node (ref "U9") (pin "82") (pinfunction "PD13_82") (pintype "passive"))
    )
    (net (code "98") (name "unconnected-(U9A-PE0-Pad141)") (class "Default")
      (node (ref "U9") (pin "141") (pinfunction "PE0_141") (pintype "passive"))
    )
    (net (code "99") (name "unconnected-(U9A-PE1-Pad142)") (class "Default")
      (node (ref "U9") (pin "142") (pinfunction "PE1_142") (pintype "passive"))
    )
    (net (code "100") (name "unconnected-(U9A-PE2-Pad1)") (class "Default")
      (node (ref "U9") (pin "1") (pinfunction "PE2_1") (pintype "passive"))
    )
    (net (code "101") (name "unconnected-(U9A-PE3-Pad2)") (class "Default")
      (node (ref "U9") (pin "2") (pinfunction "PE3_2") (pintype "passive"))
    )
    (net (code "102") (name "unconnected-(U9A-PE4-Pad3)") (class "Default")
      (node (ref "U9") (pin "3") (pinfunction "PE4_3") (pintype "passive"))
    )
    (net (code "103") (name "unconnected-(U9A-PE5-Pad4)") (class "Default")
      (node (ref "U9") (pin "4") (pinfunction "PE5_4") (pintype "passive"))
    )
    (net (code "104") (name "unconnected-(U9A-PE6-Pad5)") (class "Default")
      (node (ref "U9") (pin "5") (pinfunction "PE6_5") (pintype "passive"))
    )
    (net (code "105") (name "unconnected-(U9A-PE8-Pad59)") (class "Default")
      (node (ref "U9") (pin "59") (pinfunction "PE8_59") (pintype "passive"))
    )
    (net (code "106") (name "unconnected-(U9A-PE9-Pad60)") (class "Default")
      (node (ref "U9") (pin "60") (pinfunction "PE9_60") (pintype "passive"))
    )
    (net (code "107") (name "unconnected-(U9A-PE13-Pad66)") (class "Default")
      (node (ref "U9") (pin "66") (pinfunction "PE13_66") (pintype "passive"))
    )
    (net (code "108") (name "unconnected-(U9A-PF0-Pad10)") (class "Default")
      (node (ref "U9") (pin "10") (pinfunction "PF0_10") (pintype "passive"))
    )
    (net (code "109") (name "unconnected-(U9A-PF1-Pad11)") (class "Default")
      (node (ref "U9") (pin "11") (pinfunction "PF1_11") (pintype "passive"))
    )
    (net (code "110") (name "unconnected-(U9A-PF2-Pad12)") (class "Default")
      (node (ref "U9") (pin "12") (pinfunction "PF2_12") (pintype "passive"))
    )
    (net (code "111") (name "unconnected-(U9A-PF3-Pad13)") (class "Default")
      (node (ref "U9") (pin "13") (pinfunction "PF3_13") (pintype "passive"))
    )
    (net (code "112") (name "unconnected-(U9A-PF4-Pad14)") (class "Default")
      (node (ref "U9") (pin "14") (pinfunction "PF4_14") (pintype "passive"))
    )
    (net (code "113") (name "unconnected-(U9A-PF6-Pad18)") (class "Default")
      (node (ref "U9") (pin "18") (pinfunction "PF6_18") (pintype "passive"))
    )
    (net (code "114") (name "unconnected-(U9A-PF7-Pad19)") (class "Default")
      (node (ref "U9") (pin "19") (pinfunction "PF7_19") (pintype "passive"))
    )
    (net (code "115") (name "unconnected-(U9A-PF8-Pad20)") (class "Default")
      (node (ref "U9") (pin "20") (pinfunction "PF8_20") (pintype "passive"))
    )
    (net (code "116") (name "unconnected-(U9A-PF9-Pad21)") (class "Default")
      (node (ref "U9") (pin "21") (pinfunction "PF9_21") (pintype "passive"))
    )
    (net (code "117") (name "unconnected-(U9A-PF10-Pad22)") (class "Default")
      (node (ref "U9") (pin "22") (pinfunction "PF10_22") (pintype "passive"))
    )
    (net (code "118") (name "unconnected-(U9A-PF11-Pad49)") (class "Default")
      (node (ref "U9") (pin "49") (pinfunction "PF11_49") (pintype "passive"))
    )
    (net (code "119") (name "unconnected-(U9A-PF15-Pad55)") (class "Default")
      (node (ref "U9") (pin "55") (pinfunction "PF15_55") (pintype "passive"))
    )
    (net (code "120") (name "unconnected-(U9A-PG3-Pad88)") (class "Default")
      (node (ref "U9") (pin "88") (pinfunction "PG3_88") (pintype "passive"))
    )
    (net (code "121") (name "unconnected-(U9A-PG7-Pad92)") (class "Default")
      (node (ref "U9") (pin "92") (pinfunction "PG7_92") (pintype "passive"))
    )
    (net (code "122") (name "unconnected-(U9A-PG9-Pad124)") (class "Default")
      (node (ref "U9") (pin "124") (pinfunction "PG9_124") (pintype "passive"))
    )
    (net (code "123") (name "unconnected-(U9A-PG10-Pad125)") (class "Default")
      (node (ref "U9") (pin "125") (pinfunction "PG10_125") (pintype "passive"))
    )
    (net (code "124") (name "unconnected-(U9A-PG11-Pad126)") (class "Default")
      (node (ref "U9") (pin "126") (pinfunction "PG11_126") (pintype "passive"))
    )
    (net (code "125") (name "unconnected-(U9A-PG12-Pad127)") (class "Default")
      (node (ref "U9") (pin "127") (pinfunction "PG12_127") (pintype "passive"))
    )
    (net (code "126") (name "unconnected-(U9A-PG13-Pad128)") (class "Default")
      (node (ref "U9") (pin "128") (pinfunction "PG13_128") (pintype "passive"))
    )
    (net (code "127") (name "unconnected-(U9A-PG14-Pad129)") (class "Default")
      (node (ref "U9") (pin "129") (pinfunction "PG14_129") (pintype "passive"))
    )
    (net (code "128") (name "unconnected-(U9A-PG15-Pad132)") (class "Default")
      (node (ref "U9") (pin "132") (pinfunction "PG15_132") (pintype "passive"))
    )
    (net (code "129") (name "unconnected-(U16-VREF-Pad5)") (class "Default")
      (node (ref "U16") (pin "5") (pinfunction "VREF_5") (pintype "passive+no_connect"))
    )
  )
)
